# interface.net
KiCad netlist of a schematic drawn in Altium Designer
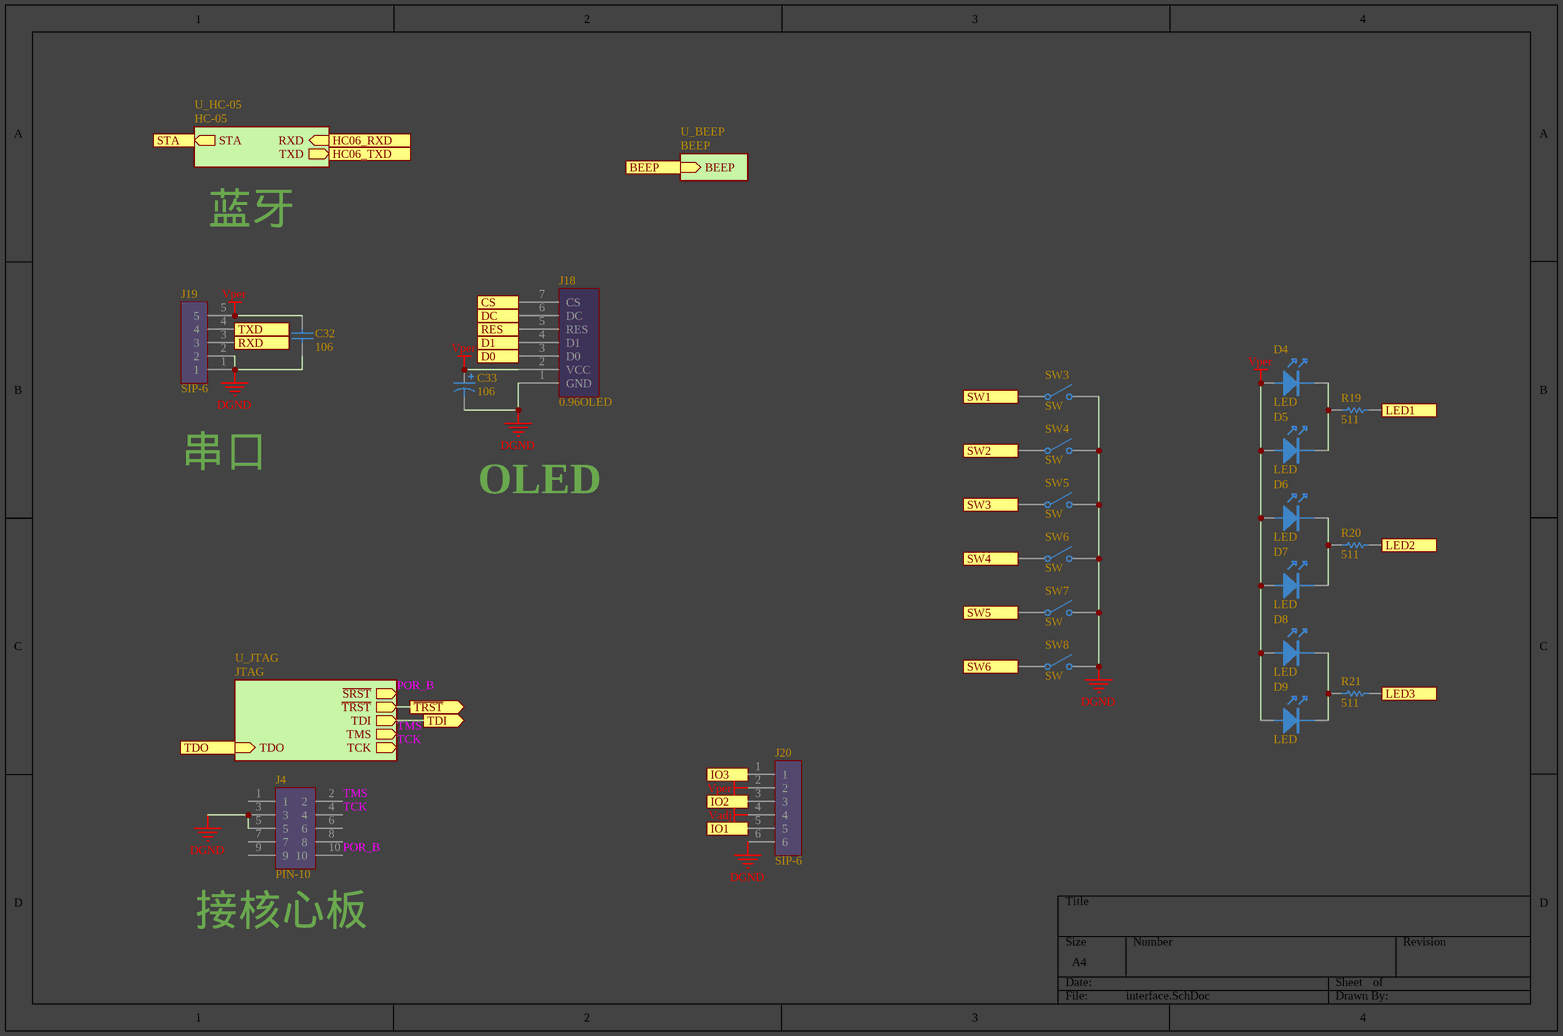
[diagram p0: interface.SchDoc]

(export (version "E")
  (design (tool "Eeschema 10.0.6"))
  (components
    (comp (ref "C32")
      (value "106")
      (footprint "C0603")
      (description "Capacitor")
      (fields (field (name "PUBLISHER") "Altium Limited"))
      (libsource (lib "iMag") (part "电容"))
    )
    (comp (ref "C33")
      (value "106")
      (footprint "3216-ce")
      (description "Polarized Capacitor (Axial)")
      (fields (field (name "PUBLISHER") "Altium Limited"))
      (libsource (lib "iMag") (part "电解电容"))
    )
    (comp (ref "D4") (value "LED") (footprint "LED-SMD_L1.7-W0.6-RD") (libsource (lib "iMag") (part "LED")))
    (comp (ref "D5") (value "LED") (footprint "LED-SMD_L1.7-W0.6-RD") (libsource (lib "iMag") (part "LED")))
    (comp (ref "D6") (value "LED") (footprint "LED-SMD_L1.7-W0.6-RD") (libsource (lib "iMag") (part "LED")))
    (comp (ref "D7") (value "LED") (footprint "LED-SMD_L1.7-W0.6-RD") (libsource (lib "iMag") (part "LED")))
    (comp (ref "D8") (value "LED") (footprint "LED-SMD_L1.7-W0.6-RD") (libsource (lib "iMag") (part "LED")))
    (comp (ref "D9") (value "LED") (footprint "LED-SMD_L1.7-W0.6-RD") (libsource (lib "iMag") (part "LED")))
    (comp (ref "J4") (value "PIN-10") (footprint "JTAG_10P") (libsource (lib "iMag") (part "PIN-10")))
    (comp (ref "J18") (value "0.96OLED") (footprint "OLED 0.96") (libsource (lib "iMag") (part "OLED_SPI")))
    (comp (ref "J19") (value "SIP-6") (footprint "2.54排针1X5") (libsource (lib "iMag") (part "SIP-5")))
    (comp (ref "J20") (value "SIP-6") (footprint "2.54简易牛角座6P") (libsource (lib "iMag") (part "SIP-6")))
    (comp (ref "R19")
      (value "511")
      (footprint "R0402")
      (description "Resistor")
      (fields (field (name "PUBLISHER") "Altium Limited"))
      (libsource (lib "iMag") (part "电阻"))
    )
    (comp (ref "R20")
      (value "511")
      (footprint "R0402")
      (description "Resistor")
      (fields (field (name "PUBLISHER") "Altium Limited"))
      (libsource (lib "iMag") (part "电阻"))
    )
    (comp (ref "R21")
      (value "511")
      (footprint "R0402")
      (description "Resistor")
      (fields (field (name "PUBLISHER") "Altium Limited"))
      (libsource (lib "iMag") (part "电阻"))
    )
    (comp (ref "SW3")
      (value "SW")
      (footprint "轻触开关6.2*6.2(5p) SMD")
      (description "Single-Pole, Single-Throw Switch")
      (libsource (lib "iMag") (part "Switch"))
    )
    (comp (ref "SW4")
      (value "SW")
      (footprint "轻触开关6.2*6.2(5p) SMD")
      (description "Single-Pole, Single-Throw Switch")
      (libsource (lib "iMag") (part "Switch"))
    )
    (comp (ref "SW5")
      (value "SW")
      (footprint "轻触开关6.2*6.2(5p) SMD")
      (description "Single-Pole, Single-Throw Switch")
      (libsource (lib "iMag") (part "Switch"))
    )
    (comp (ref "SW6")
      (value "SW")
      (footprint "轻触开关6.2*6.2(5p) SMD")
      (description "Single-Pole, Single-Throw Switch")
      (libsource (lib "iMag") (part "Switch"))
    )
    (comp (ref "SW7")
      (value "SW")
      (footprint "轻触开关6.2*6.2(5p) SMD")
      (description "Single-Pole, Single-Throw Switch")
      (libsource (lib "iMag") (part "Switch"))
    )
    (comp (ref "SW8")
      (value "SW")
      (footprint "轻触开关6.2*6.2(5p) SMD")
      (description "Single-Pole, Single-Throw Switch")
      (libsource (lib "iMag") (part "Switch"))
    )
  )
  (nets
    (net (code "2") (name "/CS") (class "Default")
      (node (ref "J18") (pin "7") (pinfunction "CS_7") (pintype "passive"))
    )
    (net (code "3") (name "/D0") (class "Default")
      (node (ref "J18") (pin "3") (pinfunction "D0_3") (pintype "passive"))
    )
    (net (code "4") (name "/D1") (class "Default")
      (node (ref "J18") (pin "4") (pinfunction "D1_4") (pintype "passive"))
    )
    (net (code "5") (name "/DC") (class "Default")
      (node (ref "J18") (pin "6") (pinfunction "DC_6") (pintype "passive"))
    )
    (net (code "8") (name "/IO1") (class "Default")
      (node (ref "J20") (pin "5") (pinfunction "5_5") (pintype "passive"))
    )
    (net (code "9") (name "/IO2") (class "Default")
      (node (ref "J20") (pin "3") (pinfunction "3_3") (pintype "passive"))
    )
    (net (code "10") (name "/IO3") (class "Default")
      (node (ref "J20") (pin "1") (pinfunction "1_1") (pintype "passive"))
    )
    (net (code "11") (name "/LED1") (class "Default")
      (node (ref "R19") (pin "1") (pinfunction "1_1") (pintype "passive"))
    )
    (net (code "12") (name "/LED2") (class "Default")
      (node (ref "R20") (pin "1") (pinfunction "1_1") (pintype "passive"))
    )
    (net (code "13") (name "/LED3") (class "Default")
      (node (ref "R21") (pin "1") (pinfunction "1_1") (pintype "passive"))
    )
    (net (code "14") (name "/POR_B") (class "Default")
      (node (ref "J4") (pin "10") (pinfunction "10_10") (pintype "passive"))
    )
    (net (code "15") (name "/RES") (class "Default")
      (node (ref "J18") (pin "5") (pinfunction "RES_5") (pintype "passive"))
    )
    (net (code "16") (name "/RXD") (class "Default")
      (node (ref "J19") (pin "3") (pinfunction "3_3") (pintype "passive"))
    )
    (net (code "18") (name "/SW1") (class "Default")
      (node (ref "SW3") (pin "1") (pinfunction "COMMON_1") (pintype "passive"))
    )
    (net (code "19") (name "/SW2") (class "Default")
      (node (ref "SW4") (pin "1") (pinfunction "COMMON_1") (pintype "passive"))
    )
    (net (code "20") (name "/SW3") (class "Default")
      (node (ref "SW5") (pin "1") (pinfunction "COMMON_1") (pintype "passive"))
    )
    (net (code "21") (name "/SW4") (class "Default")
      (node (ref "SW6") (pin "1") (pinfunction "COMMON_1") (pintype "passive"))
    )
    (net (code "22") (name "/SW5") (class "Default")
      (node (ref "SW7") (pin "1") (pinfunction "COMMON_1") (pintype "passive"))
    )
    (net (code "23") (name "/SW6") (class "Default")
      (node (ref "SW8") (pin "1") (pinfunction "COMMON_1") (pintype "passive"))
    )
    (net (code "24") (name "/TCK") (class "Default")
      (node (ref "J4") (pin "4") (pinfunction "4_4") (pintype "passive"))
    )
    (net (code "27") (name "/TMS") (class "Default")
      (node (ref "J4") (pin "2") (pinfunction "2_2") (pintype "passive"))
    )
    (net (code "29") (name "/TXD") (class "Default")
      (node (ref "J19") (pin "4") (pinfunction "4_4") (pintype "passive"))
    )
    (net (code "30") (name "DGND") (class "Default")
      (node (ref "C32") (pin "1") (pinfunction "1_1") (pintype "passive"))
      (node (ref "C33") (pin "2") (pinfunction "2_2") (pintype "passive"))
      (node (ref "J18") (pin "1") (pinfunction "GND_1") (pintype "passive"))
      (node (ref "J19") (pin "1") (pinfunction "1_1") (pintype "passive"))
      (node (ref "J19") (pin "2") (pinfunction "2_2") (pintype "passive"))
      (node (ref "J20") (pin "6") (pinfunction "6_6") (pintype "passive"))
      (node (ref "J4") (pin "3") (pinfunction "3_3") (pintype "passive"))
      (node (ref "J4") (pin "5") (pinfunction "5_5") (pintype "passive"))
      (node (ref "SW3") (pin "2") (pinfunction "NO_2") (pintype "passive"))
      (node (ref "SW4") (pin "2") (pinfunction "NO_2") (pintype "passive"))
      (node (ref "SW5") (pin "2") (pinfunction "NO_2") (pintype "passive"))
      (node (ref "SW6") (pin "2") (pinfunction "NO_2") (pintype "passive"))
      (node (ref "SW7") (pin "2") (pinfunction "NO_2") (pintype "passive"))
      (node (ref "SW8") (pin "2") (pinfunction "NO_2") (pintype "passive"))
    )
    (net (code "31") (name "Net-(D4-2)") (class "Default")
      (node (ref "D4") (pin "K") (pinfunction "2_K") (pintype "passive"))
      (node (ref "D5") (pin "K") (pinfunction "2_K") (pintype "passive"))
      (node (ref "R19") (pin "2") (pinfunction "2_2") (pintype "passive"))
    )
    (net (code "32") (name "Net-(D6-2)") (class "Default")
      (node (ref "D6") (pin "K") (pinfunction "2_K") (pintype "passive"))
      (node (ref "D7") (pin "K") (pinfunction "2_K") (pintype "passive"))
      (node (ref "R20") (pin "2") (pinfunction "2_2") (pintype "passive"))
    )
    (net (code "33") (name "Net-(D8-2)") (class "Default")
      (node (ref "D8") (pin "K") (pinfunction "2_K") (pintype "passive"))
      (node (ref "D9") (pin "K") (pinfunction "2_K") (pintype "passive"))
      (node (ref "R21") (pin "2") (pinfunction "2_2") (pintype "passive"))
    )
    (net (code "34") (name "Vadj") (class "Default")
      (node (ref "J20") (pin "4") (pinfunction "4_4") (pintype "passive"))
    )
    (net (code "35") (name "Vper") (class "Default")
      (node (ref "C32") (pin "2") (pinfunction "2_2") (pintype "passive"))
      (node (ref "C33") (pin "1") (pinfunction "1_1") (pintype "passive"))
      (node (ref "D4") (pin "A") (pinfunction "1_A") (pintype "passive"))
      (node (ref "D5") (pin "A") (pinfunction "1_A") (pintype "passive"))
      (node (ref "D6") (pin "A") (pinfunction "1_A") (pintype "passive"))
      (node (ref "D7") (pin "A") (pinfunction "1_A") (pintype "passive"))
      (node (ref "D8") (pin "A") (pinfunction "1_A") (pintype "passive"))
      (node (ref "D9") (pin "A") (pinfunction "1_A") (pintype "passive"))
      (node (ref "J18") (pin "2") (pinfunction "VCC_2") (pintype "passive"))
      (node (ref "J19") (pin "5") (pinfunction "5_5") (pintype "passive"))
      (node (ref "J20") (pin "2") (pinfunction "2_2") (pintype "passive"))
    )
    (net (code "36") (name "unconnected-(J4-Pad1)") (class "Default")
      (node (ref "J4") (pin "1") (pinfunction "1_1") (pintype "passive"))
    )
    (net (code "37") (name "unconnected-(J4-Pad6)") (class "Default")
      (node (ref "J4") (pin "6") (pinfunction "6_6") (pintype "passive"))
    )
    (net (code "38") (name "unconnected-(J4-Pad7)") (class "Default")
      (node (ref "J4") (pin "7") (pinfunction "7_7") (pintype "passive"))
    )
    (net (code "39") (name "unconnected-(J4-Pad8)") (class "Default")
      (node (ref "J4") (pin "8") (pinfunction "8_8") (pintype "passive"))
    )
    (net (code "40") (name "unconnected-(J4-Pad9)") (class "Default")
      (node (ref "J4") (pin "9") (pinfunction "9_9") (pintype "passive"))
    )
  )
)
